# Mirley_ESP8266.net
KiCad netlist of a schematic drawn in EAGLE
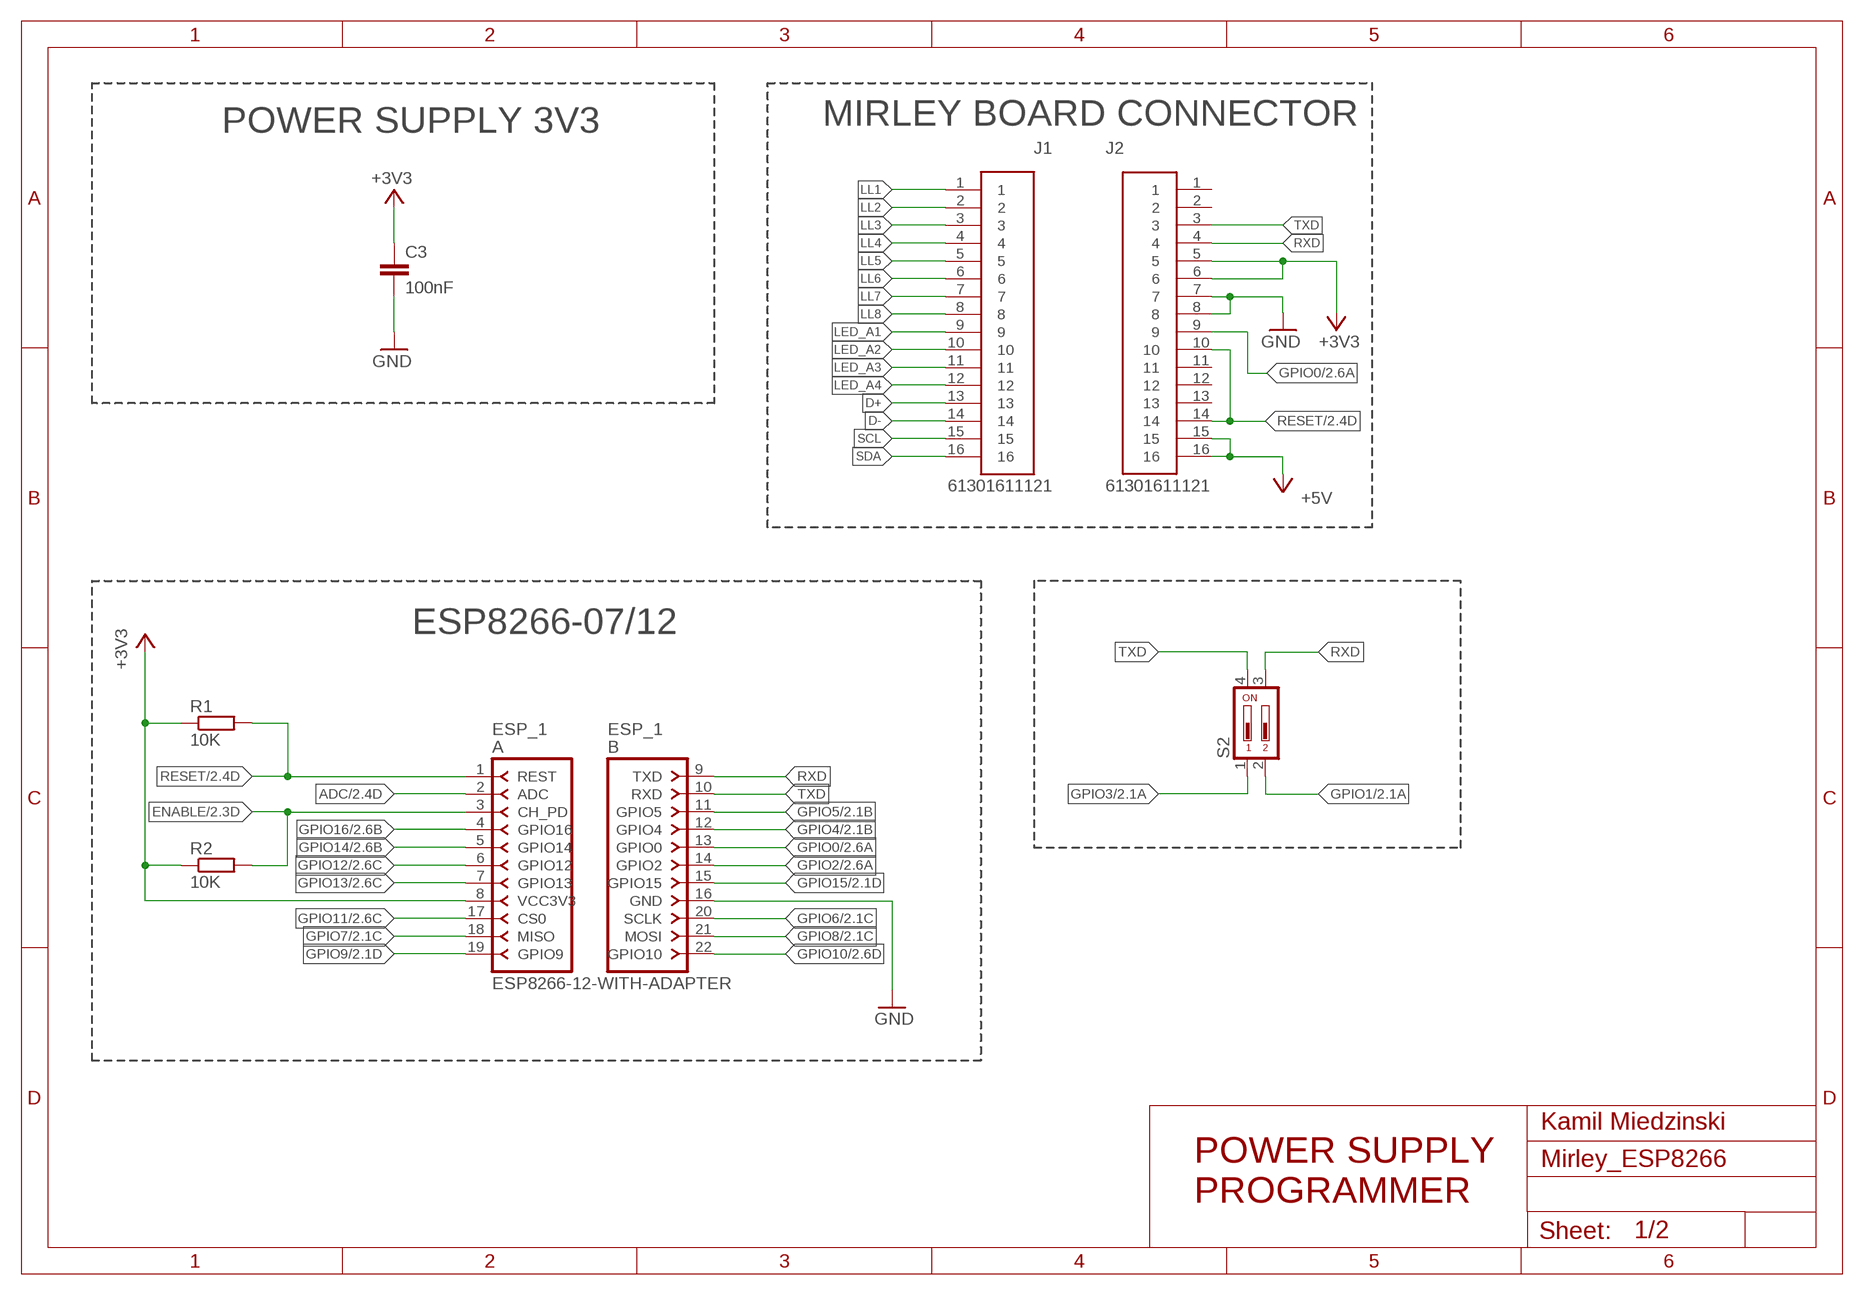
[diagram p0: schematic, sheet 1]
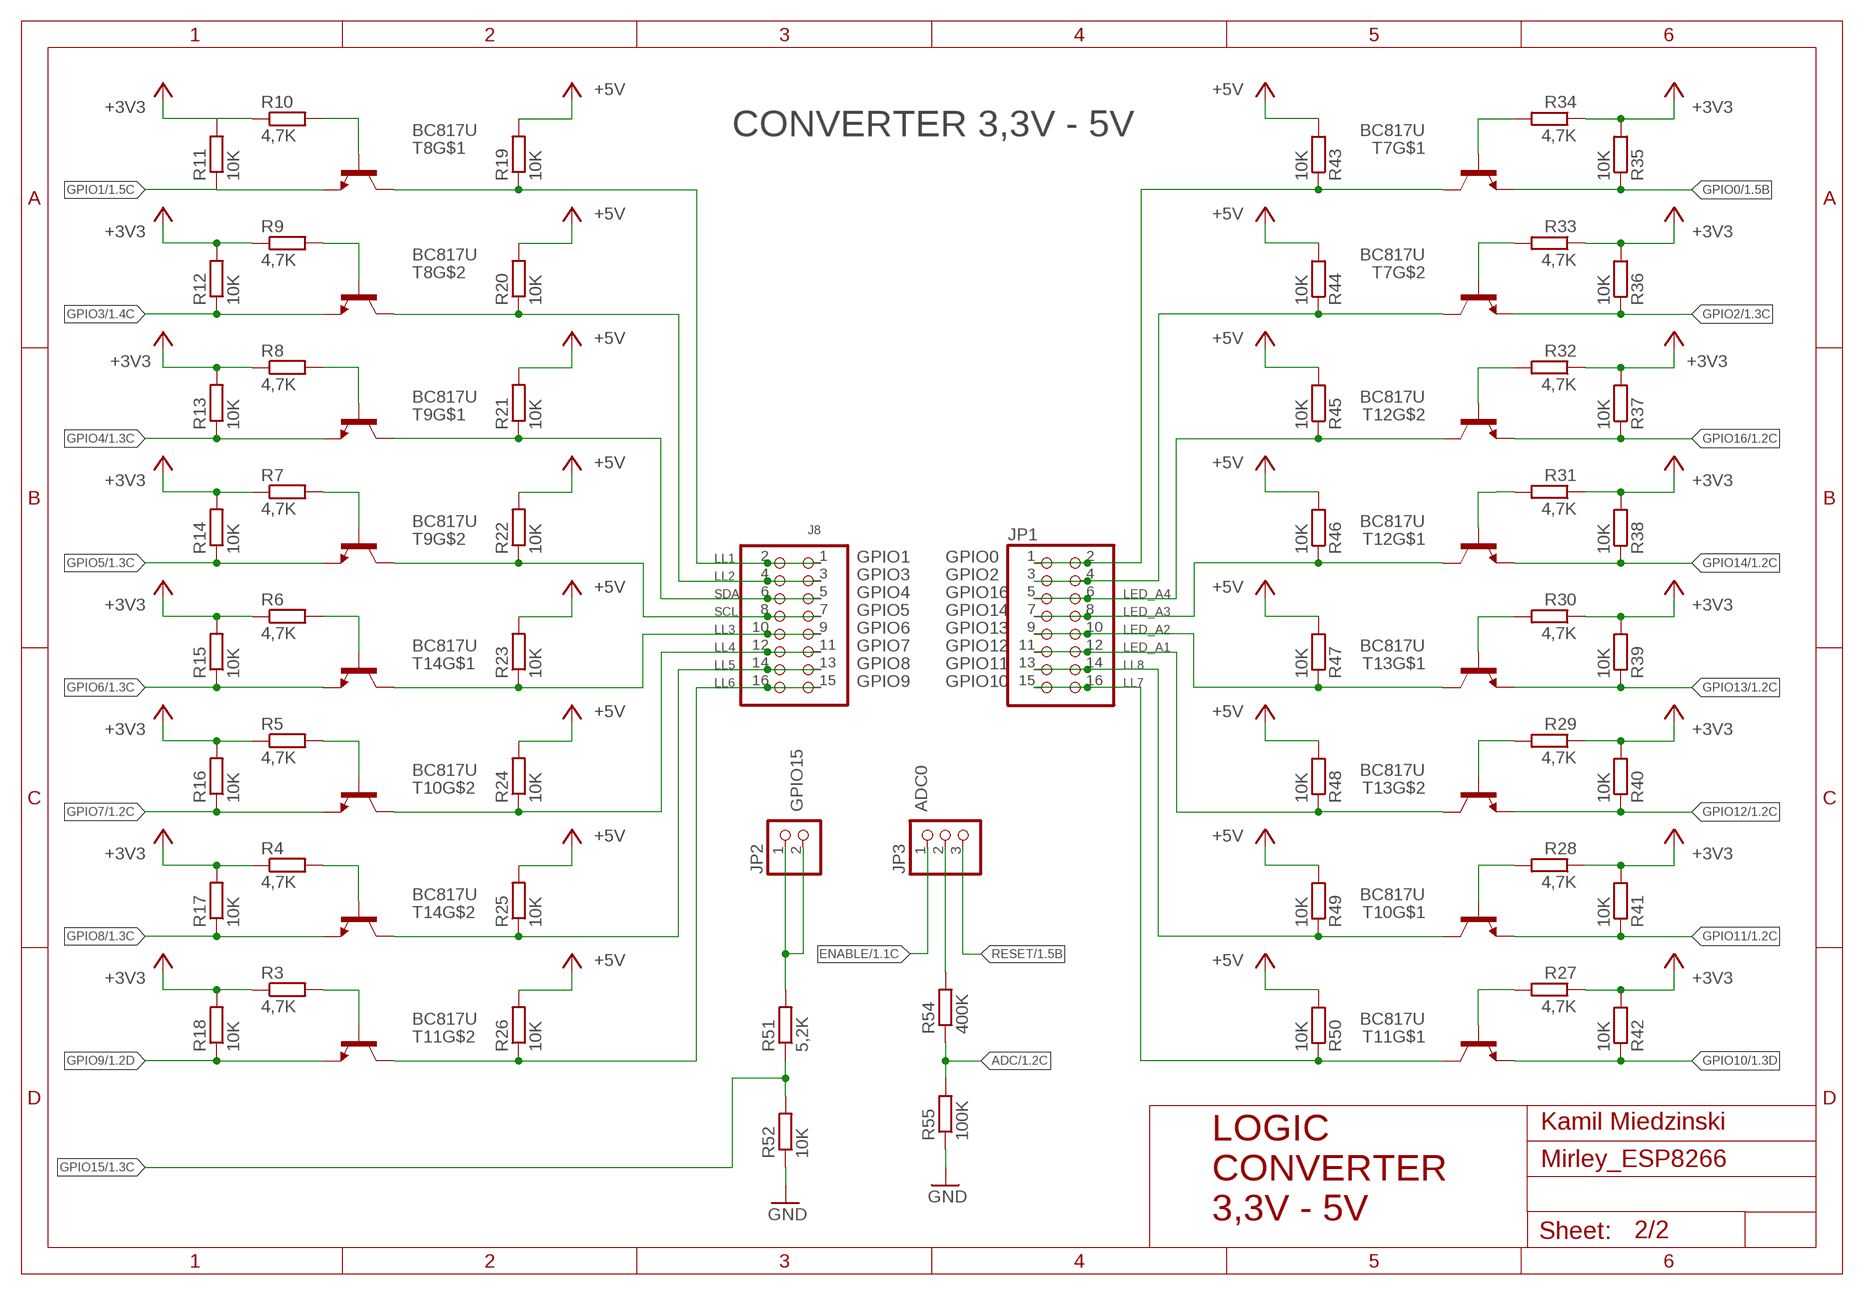
[diagram p1: schematic, sheet 2]

(export (version "E")
  (design (tool "Eeschema 10.0.6"))
  (components
    (comp (ref "C3")
      (value "100nF")
      (footprint "eagle-import:C0805K")
      (libsource (lib "eagle-import") (part "C-EUC0805K"))
    )
    (comp (ref "ESP_1")
      (value "ESP8266-12-WITH-ADAPTER")
      (footprint "eagle-import:ESP8266-12-ADAPTER")
      (libsource (lib "eagle-import") (part "ESP8266-12-WITH-ADAPTER"))
    )
    (comp (ref "J1")
      (value "61301611121")
      (footprint "eagle-import:61301611121")
      (fields
        (field (name "DIGIKEY_PART_NUMBER") "732-5327-ND")
        (field (name "MANUFACTURER") "Wurth Electronics Inc.")
        (field (name "CREATED_BY") "PCBLayout.com")
      )
      (libsource (lib "eagle-import") (part "61301611121"))
    )
    (comp (ref "J2")
      (value "61301611121")
      (footprint "eagle-import:61301611121")
      (fields
        (field (name "DIGIKEY_PART_NUMBER") "732-5327-ND")
        (field (name "MANUFACTURER") "Wurth Electronics Inc.")
        (field (name "CREATED_BY") "PCBLayout.com")
      )
      (libsource (lib "eagle-import") (part "61301611121"))
    )
    (comp (ref "R1")
      (value "10K")
      (footprint "eagle-import:R0805")
      (libsource (lib "eagle-import") (part "R-EU_R0805"))
    )
    (comp (ref "R2")
      (value "10K")
      (footprint "eagle-import:R0805")
      (libsource (lib "eagle-import") (part "R-EU_R0805"))
    )
    (comp (ref "S2")
      (value "DIP02YL")
      (footprint "eagle-import:DIP02YL")
      (libsource (lib "eagle-import") (part "DIP02YL"))
    )
    (comp (ref "J8")
      (value "PINHD-2X8")
      (footprint "eagle-import:2X08")
      (libsource (lib "eagle-import") (part "PINHD-2X8"))
    )
    (comp (ref "JP1")
      (value "PINHD-2X8")
      (footprint "eagle-import:2X08")
      (libsource (lib "eagle-import") (part "PINHD-2X8"))
    )
    (comp (ref "JP2")
      (value "PINHD-1X2")
      (footprint "eagle-import:1X02")
      (libsource (lib "eagle-import") (part "PINHD-1X2"))
    )
    (comp (ref "JP3")
      (value "PINHD-1X3")
      (footprint "eagle-import:1X03")
      (libsource (lib "eagle-import") (part "PINHD-1X3"))
    )
    (comp (ref "R3")
      (value "4,7K")
      (footprint "eagle-import:R0603")
      (libsource (lib "eagle-import") (part "R-EU_R0603"))
    )
    (comp (ref "R4")
      (value "4,7K")
      (footprint "eagle-import:R0603")
      (libsource (lib "eagle-import") (part "R-EU_R0603"))
    )
    (comp (ref "R5")
      (value "4,7K")
      (footprint "eagle-import:R0603")
      (libsource (lib "eagle-import") (part "R-EU_R0603"))
    )
    (comp (ref "R6")
      (value "4,7K")
      (footprint "eagle-import:R0603")
      (libsource (lib "eagle-import") (part "R-EU_R0603"))
    )
    (comp (ref "R7")
      (value "4,7K")
      (footprint "eagle-import:R0603")
      (libsource (lib "eagle-import") (part "R-EU_R0603"))
    )
    (comp (ref "R8")
      (value "4,7K")
      (footprint "eagle-import:R0603")
      (libsource (lib "eagle-import") (part "R-EU_R0603"))
    )
    (comp (ref "R9")
      (value "4,7K")
      (footprint "eagle-import:R0603")
      (libsource (lib "eagle-import") (part "R-EU_R0603"))
    )
    (comp (ref "R10")
      (value "4,7K")
      (footprint "eagle-import:R0603")
      (libsource (lib "eagle-import") (part "R-EU_R0603"))
    )
    (comp (ref "R11")
      (value "10K")
      (footprint "eagle-import:R0805")
      (libsource (lib "eagle-import") (part "R-EU_R0805"))
    )
    (comp (ref "R12")
      (value "10K")
      (footprint "eagle-import:R0805")
      (libsource (lib "eagle-import") (part "R-EU_R0805"))
    )
    (comp (ref "R13")
      (value "10K")
      (footprint "eagle-import:R0805")
      (libsource (lib "eagle-import") (part "R-EU_R0805"))
    )
    (comp (ref "R14")
      (value "10K")
      (footprint "eagle-import:R0805")
      (libsource (lib "eagle-import") (part "R-EU_R0805"))
    )
    (comp (ref "R15")
      (value "10K")
      (footprint "eagle-import:R0805")
      (libsource (lib "eagle-import") (part "R-EU_R0805"))
    )
    (comp (ref "R16")
      (value "10K")
      (footprint "eagle-import:R0805")
      (libsource (lib "eagle-import") (part "R-EU_R0805"))
    )
    (comp (ref "R17")
      (value "10K")
      (footprint "eagle-import:R0805")
      (libsource (lib "eagle-import") (part "R-EU_R0805"))
    )
    (comp (ref "R18")
      (value "10K")
      (footprint "eagle-import:R0805")
      (libsource (lib "eagle-import") (part "R-EU_R0805"))
    )
    (comp (ref "R19")
      (value "10K")
      (footprint "eagle-import:R0805")
      (libsource (lib "eagle-import") (part "R-EU_R0805"))
    )
    (comp (ref "R20")
      (value "10K")
      (footprint "eagle-import:R0805")
      (libsource (lib "eagle-import") (part "R-EU_R0805"))
    )
    (comp (ref "R21")
      (value "10K")
      (footprint "eagle-import:R0805")
      (libsource (lib "eagle-import") (part "R-EU_R0805"))
    )
    (comp (ref "R22")
      (value "10K")
      (footprint "eagle-import:R0805")
      (libsource (lib "eagle-import") (part "R-EU_R0805"))
    )
    (comp (ref "R23")
      (value "10K")
      (footprint "eagle-import:R0805")
      (libsource (lib "eagle-import") (part "R-EU_R0805"))
    )
    (comp (ref "R24")
      (value "10K")
      (footprint "eagle-import:R0805")
      (libsource (lib "eagle-import") (part "R-EU_R0805"))
    )
    (comp (ref "R25")
      (value "10K")
      (footprint "eagle-import:R0805")
      (libsource (lib "eagle-import") (part "R-EU_R0805"))
    )
    (comp (ref "R26")
      (value "10K")
      (footprint "eagle-import:R0805")
      (libsource (lib "eagle-import") (part "R-EU_R0805"))
    )
    (comp (ref "R27")
      (value "4,7K")
      (footprint "eagle-import:R0603")
      (libsource (lib "eagle-import") (part "R-EU_R0603"))
    )
    (comp (ref "R28")
      (value "4,7K")
      (footprint "eagle-import:R0603")
      (libsource (lib "eagle-import") (part "R-EU_R0603"))
    )
    (comp (ref "R29")
      (value "4,7K")
      (footprint "eagle-import:R0603")
      (libsource (lib "eagle-import") (part "R-EU_R0603"))
    )
    (comp (ref "R30")
      (value "4,7K")
      (footprint "eagle-import:R0603")
      (libsource (lib "eagle-import") (part "R-EU_R0603"))
    )
    (comp (ref "R31")
      (value "4,7K")
      (footprint "eagle-import:R0603")
      (libsource (lib "eagle-import") (part "R-EU_R0603"))
    )
    (comp (ref "R32")
      (value "4,7K")
      (footprint "eagle-import:R0603")
      (libsource (lib "eagle-import") (part "R-EU_R0603"))
    )
    (comp (ref "R33")
      (value "4,7K")
      (footprint "eagle-import:R0603")
      (libsource (lib "eagle-import") (part "R-EU_R0603"))
    )
    (comp (ref "R34")
      (value "4,7K")
      (footprint "eagle-import:R0603")
      (libsource (lib "eagle-import") (part "R-EU_R0603"))
    )
    (comp (ref "R35")
      (value "10K")
      (footprint "eagle-import:R0805")
      (libsource (lib "eagle-import") (part "R-EU_R0805"))
    )
    (comp (ref "R36")
      (value "10K")
      (footprint "eagle-import:R0805")
      (libsource (lib "eagle-import") (part "R-EU_R0805"))
    )
    (comp (ref "R37")
      (value "10K")
      (footprint "eagle-import:R0805")
      (libsource (lib "eagle-import") (part "R-EU_R0805"))
    )
    (comp (ref "R38")
      (value "10K")
      (footprint "eagle-import:R0805")
      (libsource (lib "eagle-import") (part "R-EU_R0805"))
    )
    (comp (ref "R39")
      (value "10K")
      (footprint "eagle-import:R0805")
      (libsource (lib "eagle-import") (part "R-EU_R0805"))
    )
    (comp (ref "R40")
      (value "10K")
      (footprint "eagle-import:R0805")
      (libsource (lib "eagle-import") (part "R-EU_R0805"))
    )
    (comp (ref "R41")
      (value "10K")
      (footprint "eagle-import:R0805")
      (libsource (lib "eagle-import") (part "R-EU_R0805"))
    )
    (comp (ref "R42")
      (value "10K")
      (footprint "eagle-import:R0805")
      (libsource (lib "eagle-import") (part "R-EU_R0805"))
    )
    (comp (ref "R43")
      (value "10K")
      (footprint "eagle-import:R0805")
      (libsource (lib "eagle-import") (part "R-EU_R0805"))
    )
    (comp (ref "R44")
      (value "10K")
      (footprint "eagle-import:R0805")
      (libsource (lib "eagle-import") (part "R-EU_R0805"))
    )
    (comp (ref "R45")
      (value "10K")
      (footprint "eagle-import:R0805")
      (libsource (lib "eagle-import") (part "R-EU_R0805"))
    )
    (comp (ref "R46")
      (value "10K")
      (footprint "eagle-import:R0805")
      (libsource (lib "eagle-import") (part "R-EU_R0805"))
    )
    (comp (ref "R47")
      (value "10K")
      (footprint "eagle-import:R0805")
      (libsource (lib "eagle-import") (part "R-EU_R0805"))
    )
    (comp (ref "R48")
      (value "10K")
      (footprint "eagle-import:R0805")
      (libsource (lib "eagle-import") (part "R-EU_R0805"))
    )
    (comp (ref "R49")
      (value "10K")
      (footprint "eagle-import:R0805")
      (libsource (lib "eagle-import") (part "R-EU_R0805"))
    )
    (comp (ref "R50")
      (value "10K")
      (footprint "eagle-import:R0805")
      (libsource (lib "eagle-import") (part "R-EU_R0805"))
    )
    (comp (ref "R51")
      (value "5,2K")
      (footprint "eagle-import:R0805")
      (libsource (lib "eagle-import") (part "R-EU_R0805"))
    )
    (comp (ref "R52")
      (value "10K")
      (footprint "eagle-import:R0805")
      (libsource (lib "eagle-import") (part "R-EU_R0805"))
    )
    (comp (ref "R54")
      (value "400K")
      (footprint "eagle-import:R0805")
      (libsource (lib "eagle-import") (part "R-EU_R0805"))
    )
    (comp (ref "R55")
      (value "100K")
      (footprint "eagle-import:R0805")
      (libsource (lib "eagle-import") (part "R-EU_R0805"))
    )
    (comp (ref "T7")
      (value "BC817U")
      (footprint "eagle-import:INF-SC74")
      (libsource (lib "eagle-import") (part "BC817U"))
    )
    (comp (ref "T8")
      (value "BC817U")
      (footprint "eagle-import:INF-SC74")
      (libsource (lib "eagle-import") (part "BC817U"))
    )
    (comp (ref "T9")
      (value "BC817U")
      (footprint "eagle-import:INF-SC74")
      (libsource (lib "eagle-import") (part "BC817U"))
    )
    (comp (ref "T10")
      (value "BC817U")
      (footprint "eagle-import:INF-SC74")
      (libsource (lib "eagle-import") (part "BC817U"))
    )
    (comp (ref "T11")
      (value "BC817U")
      (footprint "eagle-import:INF-SC74")
      (libsource (lib "eagle-import") (part "BC817U"))
    )
    (comp (ref "T12")
      (value "BC817U")
      (footprint "eagle-import:INF-SC74")
      (libsource (lib "eagle-import") (part "BC817U"))
    )
    (comp (ref "T13")
      (value "BC817U")
      (footprint "eagle-import:INF-SC74")
      (libsource (lib "eagle-import") (part "BC817U"))
    )
    (comp (ref "T14")
      (value "BC817U")
      (footprint "eagle-import:INF-SC74")
      (libsource (lib "eagle-import") (part "BC817U"))
    )
  )
  (nets
    (net (code "1") (name "+3V3") (class "Default")
      (node (ref "C3") (pin "1") (pinfunction "1_1") (pintype "passive"))
      (node (ref "ESP_1") (pin "8") (pinfunction "VCC3V3_8") (pintype "passive"))
      (node (ref "J2") (pin "5") (pinfunction "5_5") (pintype "passive"))
      (node (ref "J2") (pin "6") (pinfunction "6_6") (pintype "passive"))
      (node (ref "R1") (pin "1") (pinfunction "1_1") (pintype "passive"))
      (node (ref "R10") (pin "1") (pinfunction "1_1") (pintype "passive"))
      (node (ref "R11") (pin "2") (pinfunction "2_2") (pintype "passive"))
      (node (ref "R12") (pin "2") (pinfunction "2_2") (pintype "passive"))
      (node (ref "R13") (pin "2") (pinfunction "2_2") (pintype "passive"))
      (node (ref "R14") (pin "2") (pinfunction "2_2") (pintype "passive"))
      (node (ref "R15") (pin "2") (pinfunction "2_2") (pintype "passive"))
      (node (ref "R16") (pin "2") (pinfunction "2_2") (pintype "passive"))
      (node (ref "R17") (pin "2") (pinfunction "2_2") (pintype "passive"))
      (node (ref "R18") (pin "2") (pinfunction "2_2") (pintype "passive"))
      (node (ref "R2") (pin "1") (pinfunction "1_1") (pintype "passive"))
      (node (ref "R27") (pin "1") (pinfunction "1_1") (pintype "passive"))
      (node (ref "R28") (pin "1") (pinfunction "1_1") (pintype "passive"))
      (node (ref "R29") (pin "1") (pinfunction "1_1") (pintype "passive"))
      (node (ref "R3") (pin "1") (pinfunction "1_1") (pintype "passive"))
      (node (ref "R30") (pin "1") (pinfunction "1_1") (pintype "passive"))
      (node (ref "R31") (pin "1") (pinfunction "1_1") (pintype "passive"))
      (node (ref "R32") (pin "1") (pinfunction "1_1") (pintype "passive"))
      (node (ref "R33") (pin "1") (pinfunction "1_1") (pintype "passive"))
      (node (ref "R34") (pin "1") (pinfunction "1_1") (pintype "passive"))
      (node (ref "R35") (pin "2") (pinfunction "2_2") (pintype "passive"))
      (node (ref "R36") (pin "2") (pinfunction "2_2") (pintype "passive"))
      (node (ref "R37") (pin "2") (pinfunction "2_2") (pintype "passive"))
      (node (ref "R38") (pin "2") (pinfunction "2_2") (pintype "passive"))
      (node (ref "R39") (pin "2") (pinfunction "2_2") (pintype "passive"))
      (node (ref "R4") (pin "1") (pinfunction "1_1") (pintype "passive"))
      (node (ref "R40") (pin "2") (pinfunction "2_2") (pintype "passive"))
      (node (ref "R41") (pin "2") (pinfunction "2_2") (pintype "passive"))
      (node (ref "R42") (pin "2") (pinfunction "2_2") (pintype "passive"))
      (node (ref "R5") (pin "1") (pinfunction "1_1") (pintype "passive"))
      (node (ref "R6") (pin "1") (pinfunction "1_1") (pintype "passive"))
      (node (ref "R7") (pin "1") (pinfunction "1_1") (pintype "passive"))
      (node (ref "R8") (pin "1") (pinfunction "1_1") (pintype "passive"))
      (node (ref "R9") (pin "1") (pinfunction "1_1") (pintype "passive"))
    )
    (net (code "2") (name "+5V") (class "Default")
      (node (ref "J2") (pin "15") (pinfunction "15_15") (pintype "passive"))
      (node (ref "J2") (pin "16") (pinfunction "16_16") (pintype "passive"))
      (node (ref "R19") (pin "2") (pinfunction "2_2") (pintype "passive"))
      (node (ref "R20") (pin "2") (pinfunction "2_2") (pintype "passive"))
      (node (ref "R21") (pin "2") (pinfunction "2_2") (pintype "passive"))
      (node (ref "R22") (pin "2") (pinfunction "2_2") (pintype "passive"))
      (node (ref "R23") (pin "2") (pinfunction "2_2") (pintype "passive"))
      (node (ref "R24") (pin "2") (pinfunction "2_2") (pintype "passive"))
      (node (ref "R25") (pin "2") (pinfunction "2_2") (pintype "passive"))
      (node (ref "R26") (pin "2") (pinfunction "2_2") (pintype "passive"))
      (node (ref "R43") (pin "2") (pinfunction "2_2") (pintype "passive"))
      (node (ref "R44") (pin "2") (pinfunction "2_2") (pintype "passive"))
      (node (ref "R45") (pin "2") (pinfunction "2_2") (pintype "passive"))
      (node (ref "R46") (pin "2") (pinfunction "2_2") (pintype "passive"))
      (node (ref "R47") (pin "2") (pinfunction "2_2") (pintype "passive"))
      (node (ref "R48") (pin "2") (pinfunction "2_2") (pintype "passive"))
      (node (ref "R49") (pin "2") (pinfunction "2_2") (pintype "passive"))
      (node (ref "R50") (pin "2") (pinfunction "2_2") (pintype "passive"))
    )
    (net (code "3") (name "ADC") (class "Default")
      (node (ref "ESP_1") (pin "2") (pinfunction "ADC_2") (pintype "passive"))
      (node (ref "R54") (pin "1") (pinfunction "1_1") (pintype "passive"))
      (node (ref "R55") (pin "2") (pinfunction "2_2") (pintype "passive"))
    )
    (net (code "4") (name "D+") (class "Default")
      (node (ref "J1") (pin "13") (pinfunction "13_13") (pintype "passive"))
    )
    (net (code "5") (name "D-") (class "Default")
      (node (ref "J1") (pin "14") (pinfunction "14_14") (pintype "passive"))
    )
    (net (code "6") (name "ENABLE") (class "Default")
      (node (ref "ESP_1") (pin "3") (pinfunction "CH_PD_3") (pintype "passive"))
      (node (ref "JP3") (pin "1") (pinfunction "1_1") (pintype "passive"))
      (node (ref "R2") (pin "2") (pinfunction "2_2") (pintype "passive"))
    )
    (net (code "7") (name "GND") (class "Default")
      (node (ref "C3") (pin "2") (pinfunction "2_2") (pintype "passive"))
      (node (ref "ESP_1") (pin "16") (pinfunction "GND_16") (pintype "passive"))
      (node (ref "J2") (pin "7") (pinfunction "7_7") (pintype "passive"))
      (node (ref "J2") (pin "8") (pinfunction "8_8") (pintype "passive"))
      (node (ref "R52") (pin "1") (pinfunction "1_1") (pintype "passive"))
      (node (ref "R55") (pin "1") (pinfunction "1_1") (pintype "passive"))
    )
    (net (code "8") (name "GPIO0") (class "Default")
      (node (ref "ESP_1") (pin "13") (pinfunction "GPIO0_13") (pintype "passive"))
      (node (ref "J2") (pin "9") (pinfunction "9_9") (pintype "passive"))
      (node (ref "R35") (pin "1") (pinfunction "1_1") (pintype "passive"))
      (node (ref "T7") (pin "1") (pinfunction "E_1") (pintype "passive"))
    )
    (net (code "9") (name "GPIO1") (class "Default")
      (node (ref "R11") (pin "1") (pinfunction "1_1") (pintype "passive"))
      (node (ref "S2") (pin "2") (pinfunction "2_2") (pintype "passive"))
      (node (ref "T8") (pin "1") (pinfunction "E_1") (pintype "passive"))
    )
    (net (code "10") (name "GPIO2") (class "Default")
      (node (ref "ESP_1") (pin "14") (pinfunction "GPIO2_14") (pintype "passive"))
      (node (ref "R36") (pin "1") (pinfunction "1_1") (pintype "passive"))
      (node (ref "T7") (pin "4") (pinfunction "E_4") (pintype "passive"))
    )
    (net (code "11") (name "GPIO3") (class "Default")
      (node (ref "R12") (pin "1") (pinfunction "1_1") (pintype "passive"))
      (node (ref "S2") (pin "1") (pinfunction "1_1") (pintype "passive"))
      (node (ref "T8") (pin "4") (pinfunction "E_4") (pintype "passive"))
    )
    (net (code "12") (name "GPIO4") (class "Default")
      (node (ref "ESP_1") (pin "12") (pinfunction "GPIO4_12") (pintype "passive"))
      (node (ref "R13") (pin "1") (pinfunction "1_1") (pintype "passive"))
      (node (ref "T9") (pin "1") (pinfunction "E_1") (pintype "passive"))
    )
    (net (code "13") (name "GPIO5") (class "Default")
      (node (ref "ESP_1") (pin "11") (pinfunction "GPIO5_11") (pintype "passive"))
      (node (ref "R14") (pin "1") (pinfunction "1_1") (pintype "passive"))
      (node (ref "T9") (pin "4") (pinfunction "E_4") (pintype "passive"))
    )
    (net (code "14") (name "GPIO6") (class "Default")
      (node (ref "ESP_1") (pin "20") (pinfunction "SCLK_20") (pintype "passive"))
      (node (ref "R15") (pin "1") (pinfunction "1_1") (pintype "passive"))
      (node (ref "T14") (pin "1") (pinfunction "E_1") (pintype "passive"))
    )
    (net (code "15") (name "GPIO7") (class "Default")
      (node (ref "ESP_1") (pin "18") (pinfunction "MISO_18") (pintype "passive"))
      (node (ref "R16") (pin "1") (pinfunction "1_1") (pintype "passive"))
      (node (ref "T10") (pin "4") (pinfunction "E_4") (pintype "passive"))
    )
    (net (code "16") (name "GPIO8") (class "Default")
      (node (ref "ESP_1") (pin "21") (pinfunction "MOSI_21") (pintype "passive"))
      (node (ref "R17") (pin "1") (pinfunction "1_1") (pintype "passive"))
      (node (ref "T14") (pin "4") (pinfunction "E_4") (pintype "passive"))
    )
    (net (code "17") (name "GPIO9") (class "Default")
      (node (ref "ESP_1") (pin "19") (pinfunction "GPIO9_19") (pintype "passive"))
      (node (ref "R18") (pin "1") (pinfunction "1_1") (pintype "passive"))
      (node (ref "T11") (pin "4") (pinfunction "E_4") (pintype "passive"))
    )
    (net (code "18") (name "GPIO10") (class "Default")
      (node (ref "ESP_1") (pin "22") (pinfunction "GPIO10_22") (pintype "passive"))
      (node (ref "R42") (pin "1") (pinfunction "1_1") (pintype "passive"))
      (node (ref "T11") (pin "1") (pinfunction "E_1") (pintype "passive"))
    )
    (net (code "19") (name "GPIO11") (class "Default")
      (node (ref "ESP_1") (pin "17") (pinfunction "CS0_17") (pintype "passive"))
      (node (ref "R41") (pin "1") (pinfunction "1_1") (pintype "passive"))
      (node (ref "T10") (pin "1") (pinfunction "E_1") (pintype "passive"))
    )
    (net (code "20") (name "GPIO12") (class "Default")
      (node (ref "ESP_1") (pin "6") (pinfunction "GPIO12_6") (pintype "passive"))
      (node (ref "R40") (pin "1") (pinfunction "1_1") (pintype "passive"))
      (node (ref "T13") (pin "4") (pinfunction "E_4") (pintype "passive"))
    )
    (net (code "21") (name "GPIO13") (class "Default")
      (node (ref "ESP_1") (pin "7") (pinfunction "GPIO13_7") (pintype "passive"))
      (node (ref "R39") (pin "1") (pinfunction "1_1") (pintype "passive"))
      (node (ref "T13") (pin "1") (pinfunction "E_1") (pintype "passive"))
    )
    (net (code "22") (name "GPIO14") (class "Default")
      (node (ref "ESP_1") (pin "5") (pinfunction "GPIO14_5") (pintype "passive"))
      (node (ref "R38") (pin "1") (pinfunction "1_1") (pintype "passive"))
      (node (ref "T12") (pin "1") (pinfunction "E_1") (pintype "passive"))
    )
    (net (code "23") (name "GPIO15") (class "Default")
      (node (ref "ESP_1") (pin "15") (pinfunction "GPIO15_15") (pintype "passive"))
      (node (ref "JP2") (pin "1") (pinfunction "1_1") (pintype "passive"))
      (node (ref "JP2") (pin "2") (pinfunction "2_2") (pintype "passive"))
      (node (ref "R51") (pin "1") (pinfunction "1_1") (pintype "passive"))
      (node (ref "R51") (pin "2") (pinfunction "2_2") (pintype "passive"))
      (node (ref "R52") (pin "2") (pinfunction "2_2") (pintype "passive"))
    )
    (net (code "24") (name "GPIO16") (class "Default")
      (node (ref "ESP_1") (pin "4") (pinfunction "GPIO16_4") (pintype "passive"))
      (node (ref "R37") (pin "1") (pinfunction "1_1") (pintype "passive"))
      (node (ref "T12") (pin "4") (pinfunction "E_4") (pintype "passive"))
    )
    (net (code "25") (name "LED_A1") (class "Default")
      (node (ref "J1") (pin "9") (pinfunction "9_9") (pintype "passive"))
      (node (ref "JP1") (pin "11") (pinfunction "11_11") (pintype "passive"))
      (node (ref "JP1") (pin "12") (pinfunction "12_12") (pintype "passive"))
      (node (ref "R48") (pin "1") (pinfunction "1_1") (pintype "passive"))
      (node (ref "T13") (pin "3") (pinfunction "C_3") (pintype "passive"))
    )
    (net (code "26") (name "LED_A2") (class "Default")
      (node (ref "J1") (pin "10") (pinfunction "10_10") (pintype "passive"))
      (node (ref "JP1") (pin "10") (pinfunction "10_10") (pintype "passive"))
      (node (ref "JP1") (pin "9") (pinfunction "9_9") (pintype "passive"))
      (node (ref "R47") (pin "1") (pinfunction "1_1") (pintype "passive"))
      (node (ref "T13") (pin "6") (pinfunction "C_6") (pintype "passive"))
    )
    (net (code "27") (name "LED_A3") (class "Default")
      (node (ref "J1") (pin "11") (pinfunction "11_11") (pintype "passive"))
      (node (ref "JP1") (pin "7") (pinfunction "7_7") (pintype "passive"))
      (node (ref "JP1") (pin "8") (pinfunction "8_8") (pintype "passive"))
      (node (ref "R46") (pin "1") (pinfunction "1_1") (pintype "passive"))
      (node (ref "T12") (pin "6") (pinfunction "C_6") (pintype "passive"))
    )
    (net (code "28") (name "LED_A4") (class "Default")
      (node (ref "J1") (pin "12") (pinfunction "12_12") (pintype "passive"))
      (node (ref "JP1") (pin "5") (pinfunction "5_5") (pintype "passive"))
      (node (ref "JP1") (pin "6") (pinfunction "6_6") (pintype "passive"))
      (node (ref "R45") (pin "1") (pinfunction "1_1") (pintype "passive"))
      (node (ref "T12") (pin "3") (pinfunction "C_3") (pintype "passive"))
    )
    (net (code "29") (name "LL1") (class "Default")
      (node (ref "J1") (pin "1") (pinfunction "1_1") (pintype "passive"))
      (node (ref "J8") (pin "1") (pinfunction "1_1") (pintype "passive"))
      (node (ref "J8") (pin "2") (pinfunction "2_2") (pintype "passive"))
      (node (ref "R19") (pin "1") (pinfunction "1_1") (pintype "passive"))
      (node (ref "T8") (pin "6") (pinfunction "C_6") (pintype "passive"))
    )
    (net (code "30") (name "LL2") (class "Default")
      (node (ref "J1") (pin "2") (pinfunction "2_2") (pintype "passive"))
      (node (ref "J8") (pin "3") (pinfunction "3_3") (pintype "passive"))
      (node (ref "J8") (pin "4") (pinfunction "4_4") (pintype "passive"))
      (node (ref "R20") (pin "1") (pinfunction "1_1") (pintype "passive"))
      (node (ref "T8") (pin "3") (pinfunction "C_3") (pintype "passive"))
    )
    (net (code "31") (name "LL3") (class "Default")
      (node (ref "J1") (pin "3") (pinfunction "3_3") (pintype "passive"))
      (node (ref "J8") (pin "10") (pinfunction "10_10") (pintype "passive"))
      (node (ref "J8") (pin "9") (pinfunction "9_9") (pintype "passive"))
      (node (ref "R23") (pin "1") (pinfunction "1_1") (pintype "passive"))
      (node (ref "T14") (pin "6") (pinfunction "C_6") (pintype "passive"))
    )
    (net (code "32") (name "LL4") (class "Default")
      (node (ref "J1") (pin "4") (pinfunction "4_4") (pintype "passive"))
      (node (ref "J8") (pin "11") (pinfunction "11_11") (pintype "passive"))
      (node (ref "J8") (pin "12") (pinfunction "12_12") (pintype "passive"))
      (node (ref "R24") (pin "1") (pinfunction "1_1") (pintype "passive"))
      (node (ref "T10") (pin "3") (pinfunction "C_3") (pintype "passive"))
    )
    (net (code "33") (name "LL5") (class "Default")
      (node (ref "J1") (pin "5") (pinfunction "5_5") (pintype "passive"))
      (node (ref "J8") (pin "13") (pinfunction "13_13") (pintype "passive"))
      (node (ref "J8") (pin "14") (pinfunction "14_14") (pintype "passive"))
      (node (ref "R25") (pin "1") (pinfunction "1_1") (pintype "passive"))
      (node (ref "T14") (pin "3") (pinfunction "C_3") (pintype "passive"))
    )
    (net (code "34") (name "LL6") (class "Default")
      (node (ref "J1") (pin "6") (pinfunction "6_6") (pintype "passive"))
      (node (ref "J8") (pin "15") (pinfunction "15_15") (pintype "passive"))
      (node (ref "J8") (pin "16") (pinfunction "16_16") (pintype "passive"))
      (node (ref "R26") (pin "1") (pinfunction "1_1") (pintype "passive"))
      (node (ref "T11") (pin "3") (pinfunction "C_3") (pintype "passive"))
    )
    (net (code "35") (name "LL7") (class "Default")
      (node (ref "J1") (pin "7") (pinfunction "7_7") (pintype "passive"))
      (node (ref "JP1") (pin "15") (pinfunction "15_15") (pintype "passive"))
      (node (ref "JP1") (pin "16") (pinfunction "16_16") (pintype "passive"))
      (node (ref "R50") (pin "1") (pinfunction "1_1") (pintype "passive"))
      (node (ref "T11") (pin "6") (pinfunction "C_6") (pintype "passive"))
    )
    (net (code "36") (name "LL8") (class "Default")
      (node (ref "J1") (pin "8") (pinfunction "8_8") (pintype "passive"))
      (node (ref "JP1") (pin "13") (pinfunction "13_13") (pintype "passive"))
      (node (ref "JP1") (pin "14") (pinfunction "14_14") (pintype "passive"))
      (node (ref "R49") (pin "1") (pinfunction "1_1") (pintype "passive"))
      (node (ref "T10") (pin "6") (pinfunction "C_6") (pintype "passive"))
    )
    (net (code "37") (name "Net-(JP3-Pad2)") (class "Default")
      (node (ref "JP3") (pin "2") (pinfunction "2_2") (pintype "passive"))
      (node (ref "R54") (pin "2") (pinfunction "2_2") (pintype "passive"))
    )
    (net (code "38") (name "Net-(T7A-B)") (class "Default")
      (node (ref "R34") (pin "2") (pinfunction "2_2") (pintype "passive"))
      (node (ref "T7") (pin "2") (pinfunction "B_2") (pintype "passive"))
    )
    (net (code "39") (name "Net-(T7A-C)") (class "Default")
      (node (ref "JP1") (pin "1") (pinfunction "1_1") (pintype "passive"))
      (node (ref "JP1") (pin "2") (pinfunction "2_2") (pintype "passive"))
      (node (ref "R43") (pin "1") (pinfunction "1_1") (pintype "passive"))
      (node (ref "T7") (pin "6") (pinfunction "C_6") (pintype "passive"))
    )
    (net (code "40") (name "Net-(T7B-B)") (class "Default")
      (node (ref "R33") (pin "2") (pinfunction "2_2") (pintype "passive"))
      (node (ref "T7") (pin "5") (pinfunction "B_5") (pintype "passive"))
    )
    (net (code "41") (name "Net-(T7B-C)") (class "Default")
      (node (ref "JP1") (pin "3") (pinfunction "3_3") (pintype "passive"))
      (node (ref "JP1") (pin "4") (pinfunction "4_4") (pintype "passive"))
      (node (ref "R44") (pin "1") (pinfunction "1_1") (pintype "passive"))
      (node (ref "T7") (pin "3") (pinfunction "C_3") (pintype "passive"))
    )
    (net (code "42") (name "Net-(T8A-B)") (class "Default")
      (node (ref "R10") (pin "2") (pinfunction "2_2") (pintype "passive"))
      (node (ref "T8") (pin "2") (pinfunction "B_2") (pintype "passive"))
    )
    (net (code "43") (name "Net-(T8B-B)") (class "Default")
      (node (ref "R9") (pin "2") (pinfunction "2_2") (pintype "passive"))
      (node (ref "T8") (pin "5") (pinfunction "B_5") (pintype "passive"))
    )
    (net (code "44") (name "Net-(T9A-B)") (class "Default")
      (node (ref "R8") (pin "2") (pinfunction "2_2") (pintype "passive"))
      (node (ref "T9") (pin "2") (pinfunction "B_2") (pintype "passive"))
    )
    (net (code "45") (name "Net-(T9B-B)") (class "Default")
      (node (ref "R7") (pin "2") (pinfunction "2_2") (pintype "passive"))
      (node (ref "T9") (pin "5") (pinfunction "B_5") (pintype "passive"))
    )
    (net (code "46") (name "Net-(T10A-B)") (class "Default")
      (node (ref "R28") (pin "2") (pinfunction "2_2") (pintype "passive"))
      (node (ref "T10") (pin "2") (pinfunction "B_2") (pintype "passive"))
    )
    (net (code "47") (name "Net-(T10B-B)") (class "Default")
      (node (ref "R5") (pin "2") (pinfunction "2_2") (pintype "passive"))
      (node (ref "T10") (pin "5") (pinfunction "B_5") (pintype "passive"))
    )
    (net (code "48") (name "Net-(T11A-B)") (class "Default")
      (node (ref "R27") (pin "2") (pinfunction "2_2") (pintype "passive"))
      (node (ref "T11") (pin "2") (pinfunction "B_2") (pintype "passive"))
    )
    (net (code "49") (name "Net-(T11B-B)") (class "Default")
      (node (ref "R3") (pin "2") (pinfunction "2_2") (pintype "passive"))
      (node (ref "T11") (pin "5") (pinfunction "B_5") (pintype "passive"))
    )
    (net (code "50") (name "Net-(T12A-B)") (class "Default")
      (node (ref "R31") (pin "2") (pinfunction "2_2") (pintype "passive"))
      (node (ref "T12") (pin "2") (pinfunction "B_2") (pintype "passive"))
    )
    (net (code "51") (name "Net-(T12B-B)") (class "Default")
      (node (ref "R32") (pin "2") (pinfunction "2_2") (pintype "passive"))
      (node (ref "T12") (pin "5") (pinfunction "B_5") (pintype "passive"))
    )
    (net (code "52") (name "Net-(T13A-B)") (class "Default")
      (node (ref "R30") (pin "2") (pinfunction "2_2") (pintype "passive"))
      (node (ref "T13") (pin "2") (pinfunction "B_2") (pintype "passive"))
    )
    (net (code "53") (name "Net-(T13B-B)") (class "Default")
      (node (ref "R29") (pin "2") (pinfunction "2_2") (pintype "passive"))
      (node (ref "T13") (pin "5") (pinfunction "B_5") (pintype "passive"))
    )
    (net (code "54") (name "Net-(T14A-B)") (class "Default")
      (node (ref "R6") (pin "2") (pinfunction "2_2") (pintype "passive"))
      (node (ref "T14") (pin "2") (pinfunction "B_2") (pintype "passive"))
    )
    (net (code "55") (name "Net-(T14B-B)") (class "Default")
      (node (ref "R4") (pin "2") (pinfunction "2_2") (pintype "passive"))
      (node (ref "T14") (pin "5") (pinfunction "B_5") (pintype "passive"))
    )
    (net (code "56") (name "RESET") (class "Default")
      (node (ref "ESP_1") (pin "1") (pinfunction "REST_1") (pintype "passive"))
      (node (ref "J2") (pin "10") (pinfunction "10_10") (pintype "passive"))
      (node (ref "J2") (pin "14") (pinfunction "14_14") (pintype "passive"))
      (node (ref "JP3") (pin "3") (pinfunction "3_3") (pintype "passive"))
      (node (ref "R1") (pin "2") (pinfunction "2_2") (pintype "passive"))
    )
    (net (code "57") (name "RXD") (class "Default")
      (node (ref "ESP_1") (pin "9") (pinfunction "TXD_9") (pintype "passive"))
      (node (ref "J2") (pin "4") (pinfunction "4_4") (pintype "passive"))
      (node (ref "S2") (pin "3") (pinfunction "3_3") (pintype "passive"))
    )
    (net (code "58") (name "SCL") (class "Default")
      (node (ref "J1") (pin "15") (pinfunction "15_15") (pintype "passive"))
      (node (ref "J8") (pin "7") (pinfunction "7_7") (pintype "passive"))
      (node (ref "J8") (pin "8") (pinfunction "8_8") (pintype "passive"))
      (node (ref "R22") (pin "1") (pinfunction "1_1") (pintype "passive"))
      (node (ref "T9") (pin "3") (pinfunction "C_3") (pintype "passive"))
    )
    (net (code "59") (name "SDA") (class "Default")
      (node (ref "J1") (pin "16") (pinfunction "16_16") (pintype "passive"))
      (node (ref "J8") (pin "5") (pinfunction "5_5") (pintype "passive"))
      (node (ref "J8") (pin "6") (pinfunction "6_6") (pintype "passive"))
      (node (ref "R21") (pin "1") (pinfunction "1_1") (pintype "passive"))
      (node (ref "T9") (pin "6") (pinfunction "C_6") (pintype "passive"))
    )
    (net (code "60") (name "TXD") (class "Default")
      (node (ref "ESP_1") (pin "10") (pinfunction "RXD_10") (pintype "passive"))
      (node (ref "J2") (pin "3") (pinfunction "3_3") (pintype "passive"))
      (node (ref "S2") (pin "4") (pinfunction "4_4") (pintype "passive"))
    )
    (net (code "61") (name "unconnected-(J2-Pad1)") (class "Default")
      (node (ref "J2") (pin "1") (pinfunction "1_1") (pintype "passive"))
    )
    (net (code "62") (name "unconnected-(J2-Pad2)") (class "Default")
      (node (ref "J2") (pin "2") (pinfunction "2_2") (pintype "passive"))
    )
    (net (code "63") (name "unconnected-(J2-Pad11)") (class "Default")
      (node (ref "J2") (pin "11") (pinfunction "11_11") (pintype "passive"))
    )
    (net (code "64") (name "unconnected-(J2-Pad12)") (class "Default")
      (node (ref "J2") (pin "12") (pinfunction "12_12") (pintype "passive"))
    )
    (net (code "65") (name "unconnected-(J2-Pad13)") (class "Default")
      (node (ref "J2") (pin "13") (pinfunction "13_13") (pintype "passive"))
    )
  )
)
